# EchidnaShield_000.net
KiCad netlist of a schematic drawn in EAGLE
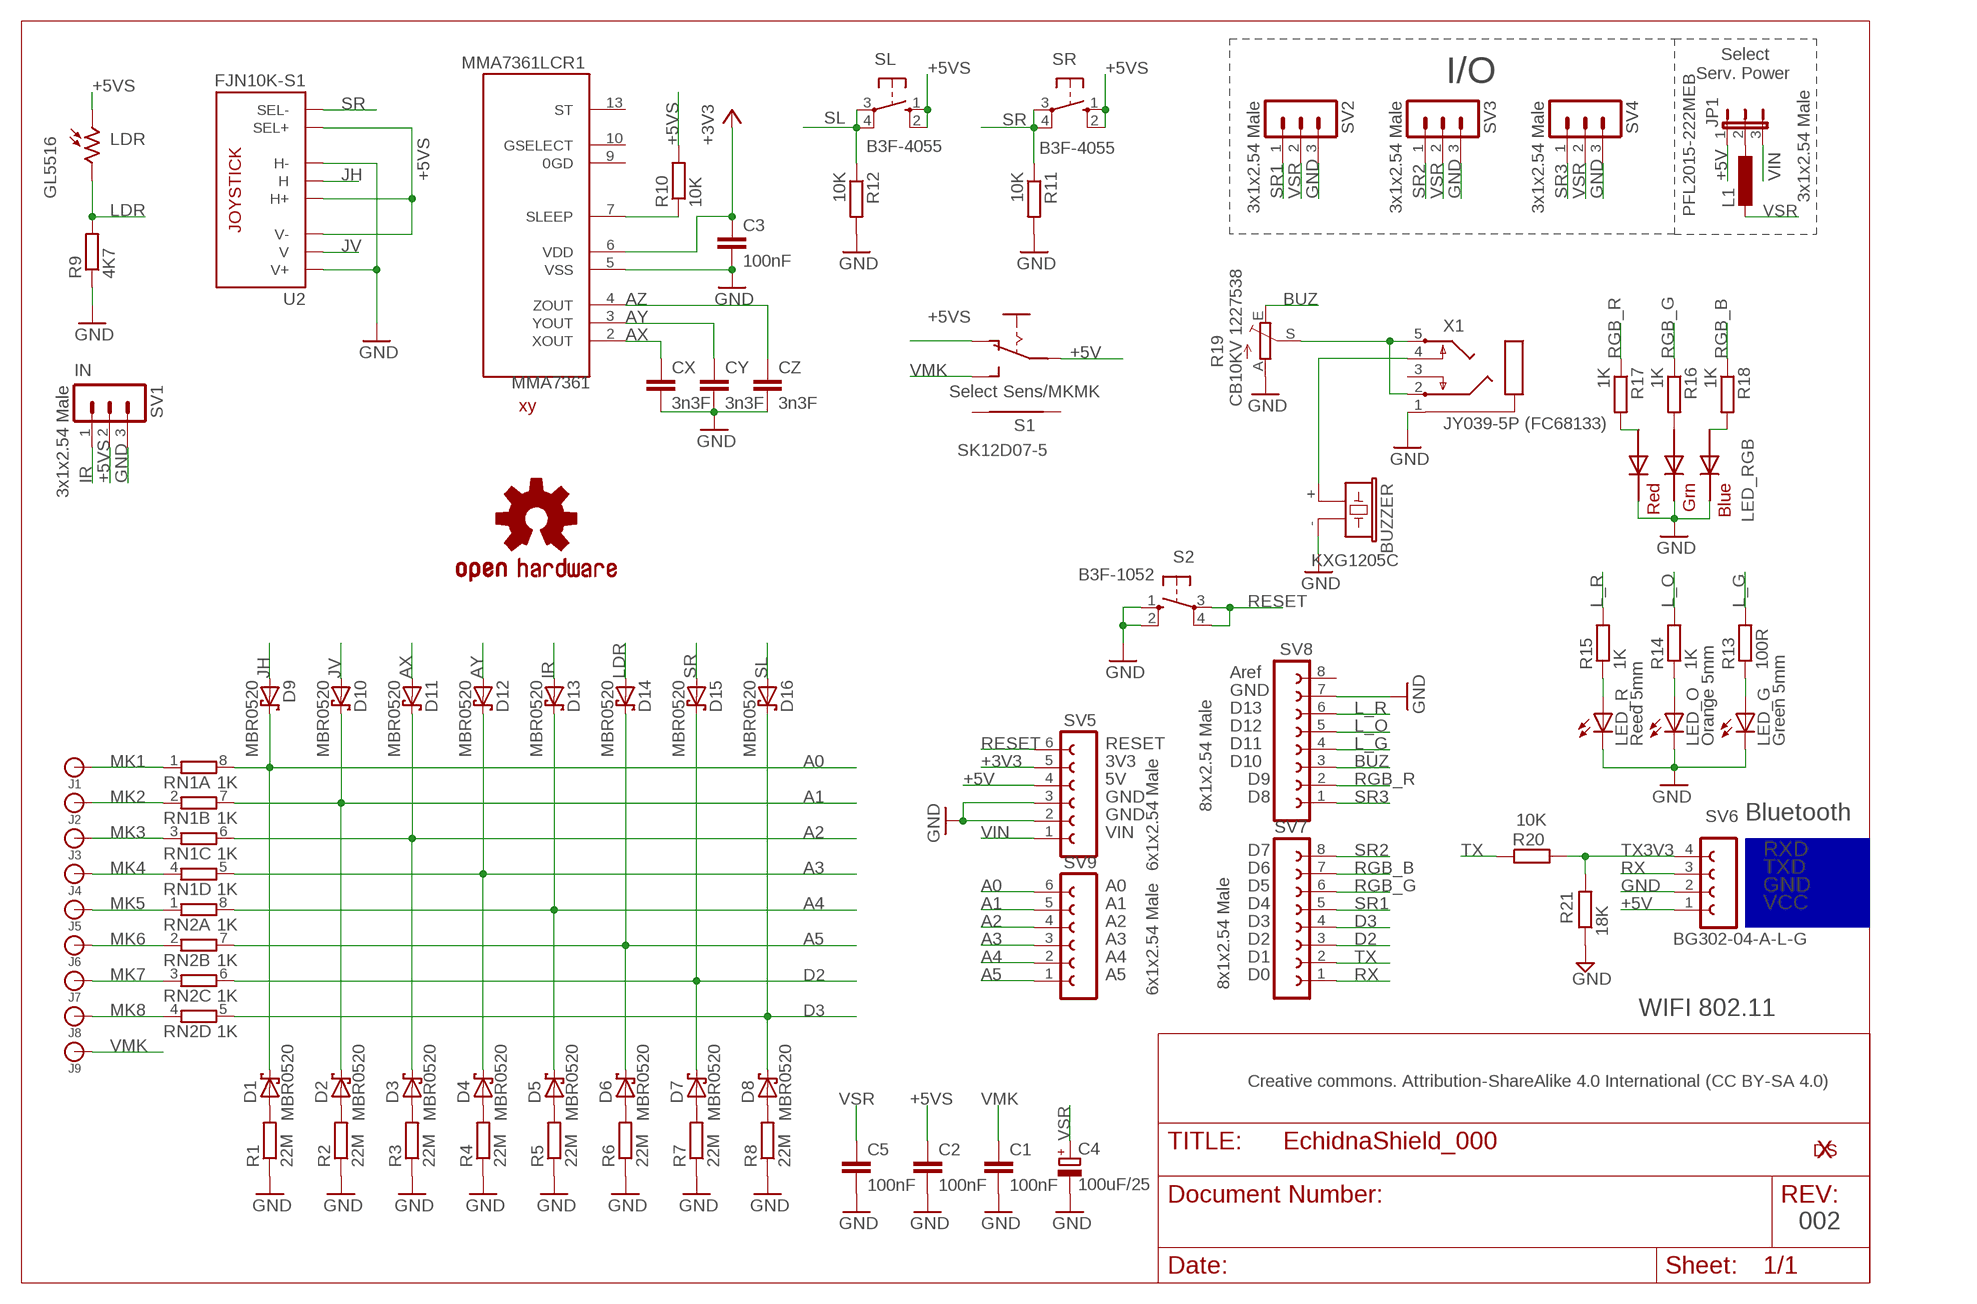
[diagram p0: schematic, sheet 1]

(export (version "E")
  (design (tool "Eeschema 10.0.6"))
  (components
    (comp (ref "BUZZER")
      (value "KXG1205C")
      (footprint "eagle-import:F_CM12P")
      (libsource (lib "eagle-import") (part "F/CM12P"))
    )
    (comp (ref "C1")
      (value "100nF")
      (footprint "eagle-import:C0603K")
      (libsource (lib "eagle-import") (part "C-EUC0603K"))
    )
    (comp (ref "C2")
      (value "100nF")
      (footprint "eagle-import:C0603K")
      (libsource (lib "eagle-import") (part "C-EUC0603K"))
    )
    (comp (ref "C3")
      (value "100nF")
      (footprint "eagle-import:C0603K")
      (libsource (lib "eagle-import") (part "C-EUC0603K"))
    )
    (comp (ref "C4")
      (value "100uF/25")
      (footprint "eagle-import:PANASONIC_D")
      (libsource (lib "eagle-import") (part "CPOL-EUD"))
    )
    (comp (ref "C5")
      (value "100nF")
      (footprint "eagle-import:C0603K")
      (libsource (lib "eagle-import") (part "C-EUC0603K"))
    )
    (comp (ref "CX")
      (value "3n3F")
      (footprint "eagle-import:C0603K")
      (libsource (lib "eagle-import") (part "C-EUC0603K"))
    )
    (comp (ref "CY")
      (value "3n3F")
      (footprint "eagle-import:C0603K")
      (libsource (lib "eagle-import") (part "C-EUC0603K"))
    )
    (comp (ref "CZ")
      (value "3n3F")
      (footprint "eagle-import:C0603K")
      (libsource (lib "eagle-import") (part "C-EUC0603K"))
    )
    (comp (ref "D1")
      (value "MBR0520")
      (footprint "eagle-import:SOD123FL")
      (libsource (lib "eagle-import") (part "SCHOTTKY-DIODESOD123FL"))
    )
    (comp (ref "D2")
      (value "MBR0520")
      (footprint "eagle-import:SOD123FL")
      (libsource (lib "eagle-import") (part "SCHOTTKY-DIODESOD123FL"))
    )
    (comp (ref "D3")
      (value "MBR0520")
      (footprint "eagle-import:SOD123FL")
      (libsource (lib "eagle-import") (part "SCHOTTKY-DIODESOD123FL"))
    )
    (comp (ref "D4")
      (value "MBR0520")
      (footprint "eagle-import:SOD123FL")
      (libsource (lib "eagle-import") (part "SCHOTTKY-DIODESOD123FL"))
    )
    (comp (ref "D5")
      (value "MBR0520")
      (footprint "eagle-import:SOD123FL")
      (libsource (lib "eagle-import") (part "SCHOTTKY-DIODESOD123FL"))
    )
    (comp (ref "D6")
      (value "MBR0520")
      (footprint "eagle-import:SOD123FL")
      (libsource (lib "eagle-import") (part "SCHOTTKY-DIODESOD123FL"))
    )
    (comp (ref "D7")
      (value "MBR0520")
      (footprint "eagle-import:SOD123FL")
      (libsource (lib "eagle-import") (part "SCHOTTKY-DIODESOD123FL"))
    )
    (comp (ref "D8")
      (value "MBR0520")
      (footprint "eagle-import:SOD123FL")
      (libsource (lib "eagle-import") (part "SCHOTTKY-DIODESOD123FL"))
    )
    (comp (ref "D9")
      (value "MBR0520")
      (footprint "eagle-import:SOD123FL")
      (libsource (lib "eagle-import") (part "SCHOTTKY-DIODESOD123FL"))
    )
    (comp (ref "D10")
      (value "MBR0520")
      (footprint "eagle-import:SOD123FL")
      (libsource (lib "eagle-import") (part "SCHOTTKY-DIODESOD123FL"))
    )
    (comp (ref "D11")
      (value "MBR0520")
      (footprint "eagle-import:SOD123FL")
      (libsource (lib "eagle-import") (part "SCHOTTKY-DIODESOD123FL"))
    )
    (comp (ref "D12")
      (value "MBR0520")
      (footprint "eagle-import:SOD123FL")
      (libsource (lib "eagle-import") (part "SCHOTTKY-DIODESOD123FL"))
    )
    (comp (ref "D13")
      (value "MBR0520")
      (footprint "eagle-import:SOD123FL")
      (libsource (lib "eagle-import") (part "SCHOTTKY-DIODESOD123FL"))
    )
    (comp (ref "D14")
      (value "MBR0520")
      (footprint "eagle-import:SOD123FL")
      (libsource (lib "eagle-import") (part "SCHOTTKY-DIODESOD123FL"))
    )
    (comp (ref "D15")
      (value "MBR0520")
      (footprint "eagle-import:SOD123FL")
      (libsource (lib "eagle-import") (part "SCHOTTKY-DIODESOD123FL"))
    )
    (comp (ref "D16")
      (value "MBR0520")
      (footprint "eagle-import:SOD123FL")
      (libsource (lib "eagle-import") (part "SCHOTTKY-DIODESOD123FL"))
    )
    (comp (ref "J1")
      (value "Hole")
      (footprint "eagle-import:BANANA_CONN")
      (libsource (lib "eagle-import") (part "BANANA_CONN"))
    )
    (comp (ref "J2")
      (value "Hole")
      (footprint "eagle-import:BANANA_CONN")
      (libsource (lib "eagle-import") (part "BANANA_CONN"))
    )
    (comp (ref "J3")
      (value "Hole")
      (footprint "eagle-import:BANANA_CONN")
      (libsource (lib "eagle-import") (part "BANANA_CONN"))
    )
    (comp (ref "J4")
      (value "Hole")
      (footprint "eagle-import:BANANA_CONN")
      (libsource (lib "eagle-import") (part "BANANA_CONN"))
    )
    (comp (ref "J5")
      (value "Hole")
      (footprint "eagle-import:BANANA_CONN")
      (libsource (lib "eagle-import") (part "BANANA_CONN"))
    )
    (comp (ref "J6")
      (value "Hole")
      (footprint "eagle-import:BANANA_CONN")
      (libsource (lib "eagle-import") (part "BANANA_CONN"))
    )
    (comp (ref "J7")
      (value "Hole")
      (footprint "eagle-import:BANANA_CONN")
      (libsource (lib "eagle-import") (part "BANANA_CONN"))
    )
    (comp (ref "J8")
      (value "Hole")
      (footprint "eagle-import:BANANA_CONN")
      (libsource (lib "eagle-import") (part "BANANA_CONN"))
    )
    (comp (ref "J9")
      (value "Hole")
      (footprint "eagle-import:BANANA_CONN")
      (libsource (lib "eagle-import") (part "BANANA_CONN"))
    )
    (comp (ref "JP1")
      (value "3x1x2.54 Male")
      (footprint "eagle-import:JUMPER_JP2")
      (libsource (lib "eagle-import") (part "JUMPER_JP2E"))
    )
    (comp (ref "L1")
      (value "PFL2015-222MEB")
      (footprint "eagle-import:L3216C")
      (libsource (lib "eagle-import") (part "L-EUL3216C"))
    )
    (comp (ref "LDR")
      (value "GL5516")
      (footprint "eagle-import:T0-46-A10XX")
      (libsource (lib "eagle-import") (part "A1060_34"))
    )
    (comp (ref "LED_G")
      (value "Green 5mm")
      (footprint "eagle-import:LED5MM")
      (libsource (lib "eagle-import") (part "LED5MM"))
    )
    (comp (ref "LED_O")
      (value "Orange 5mm")
      (footprint "eagle-import:LED5MM")
      (libsource (lib "eagle-import") (part "LED5MM"))
    )
    (comp (ref "LED_R")
      (value "Reed 5mm")
      (footprint "eagle-import:LED5MM")
      (libsource (lib "eagle-import") (part "LED5MM"))
    )
    (comp (ref "LED_RGB")
      (value "CPL6C-FKBN")
      (footprint "eagle-import:PLCC6")
      (libsource (lib "eagle-import") (part "CPL6C-FKBN"))
    )
    (comp (ref "LOGO1")
      (value "SPARKFUN-AESTHETICS_OSHW-LOGOL")
      (footprint "eagle-import:SPARKFUN-AESTHETICS_OSHW-LOGO-L")
      (libsource (lib "eagle-import") (part "SPARKFUN-AESTHETICS_OSHW-LOGOL"))
    )
    (comp (ref "MMA7361")
      (value "MMA7361LCR1")
      (footprint "eagle-import:LGA14")
      (libsource (lib "eagle-import") (part "MMA7361"))
    )
    (comp (ref "R1")
      (value "22M")
      (footprint "eagle-import:RCL_R0603")
      (libsource (lib "eagle-import") (part "RCL_R-EU_R0603"))
    )
    (comp (ref "R2")
      (value "22M")
      (footprint "eagle-import:RCL_R0603")
      (libsource (lib "eagle-import") (part "RCL_R-EU_R0603"))
    )
    (comp (ref "R3")
      (value "22M")
      (footprint "eagle-import:RCL_R0603")
      (libsource (lib "eagle-import") (part "RCL_R-EU_R0603"))
    )
    (comp (ref "R4")
      (value "22M")
      (footprint "eagle-import:RCL_R0603")
      (libsource (lib "eagle-import") (part "RCL_R-EU_R0603"))
    )
    (comp (ref "R5")
      (value "22M")
      (footprint "eagle-import:RCL_R0603")
      (libsource (lib "eagle-import") (part "RCL_R-EU_R0603"))
    )
    (comp (ref "R6")
      (value "22M")
      (footprint "eagle-import:RCL_R0603")
      (libsource (lib "eagle-import") (part "RCL_R-EU_R0603"))
    )
    (comp (ref "R7")
      (value "22M")
      (footprint "eagle-import:RCL_R0603")
      (libsource (lib "eagle-import") (part "RCL_R-EU_R0603"))
    )
    (comp (ref "R8")
      (value "22M")
      (footprint "eagle-import:RCL_R0603")
      (libsource (lib "eagle-import") (part "RCL_R-EU_R0603"))
    )
    (comp (ref "R9")
      (value "4K7")
      (footprint "eagle-import:RCL_R0603")
      (libsource (lib "eagle-import") (part "RCL_R-EU_R0603"))
    )
    (comp (ref "R10")
      (value "10K")
      (footprint "eagle-import:RCL_R0603")
      (libsource (lib "eagle-import") (part "RCL_R-EU_R0603"))
    )
    (comp (ref "R11")
      (value "10K")
      (footprint "eagle-import:RCL_R0603")
      (libsource (lib "eagle-import") (part "RCL_R-EU_R0603"))
    )
    (comp (ref "R12")
      (value "10K")
      (footprint "eagle-import:RCL_R0603")
      (libsource (lib "eagle-import") (part "RCL_R-EU_R0603"))
    )
    (comp (ref "R13")
      (value "100R")
      (footprint "eagle-import:RCL_R0603")
      (libsource (lib "eagle-import") (part "RCL_R-EU_R0603"))
    )
    (comp (ref "R14")
      (value "1K")
      (footprint "eagle-import:RCL_R0603")
      (libsource (lib "eagle-import") (part "RCL_R-EU_R0603"))
    )
    (comp (ref "R15")
      (value "1K")
      (footprint "eagle-import:RCL_R0603")
      (libsource (lib "eagle-import") (part "RCL_R-EU_R0603"))
    )
    (comp (ref "R16")
      (value "1K")
      (footprint "eagle-import:RCL_R0603")
      (libsource (lib "eagle-import") (part "RCL_R-EU_R0603"))
    )
    (comp (ref "R17")
      (value "1K")
      (footprint "eagle-import:RCL_R0603")
      (libsource (lib "eagle-import") (part "RCL_R-EU_R0603"))
    )
    (comp (ref "R18")
      (value "1K")
      (footprint "eagle-import:RCL_R0603")
      (libsource (lib "eagle-import") (part "RCL_R-EU_R0603"))
    )
    (comp (ref "R19")
      (value "CB10KV 1227538")
      (footprint "eagle-import:CA9V")
      (libsource (lib "eagle-import") (part "TRIM_EU-CA9V"))
    )
    (comp (ref "R20")
      (value "10K")
      (footprint "eagle-import:R0603")
      (libsource (lib "eagle-import") (part "R-EU_R0603"))
    )
    (comp (ref "R21")
      (value "18K")
      (footprint "eagle-import:R0603")
      (libsource (lib "eagle-import") (part "R-EU_R0603"))
    )
    (comp (ref "RN1")
      (value "1K")
      (footprint "eagle-import:RESISTOR-DIL_0603-ARC")
      (libsource (lib "eagle-import") (part "RESISTOR-DIL_4R-N0603-ARC"))
    )
    (comp (ref "RN2")
      (value "1K")
      (footprint "eagle-import:RESISTOR-DIL_0603-ARC")
      (libsource (lib "eagle-import") (part "RESISTOR-DIL_4R-N0603-ARC"))
    )
    (comp (ref "S1")
      (value "SK12D07-5")
      (footprint "eagle-import:ESCORNA_SK-12D07")
      (libsource (lib "eagle-import") (part "ESCORNA_SK12F14D"))
    )
    (comp (ref "S2")
      (value "B3F-1052")
      (footprint "eagle-import:SWITCH-OMRON_B3F-10XX")
      (fields (field (name "MPN") "B3F-1000"))
      (libsource (lib "eagle-import") (part "SWITCH-OMRON_10-XX"))
    )
    (comp (ref "SL")
      (value "B3F-4055")
      (footprint "eagle-import:B3F-40XX")
      (fields (field (name "MF") "OMRON COMPONENTS USA") (field (name "MPN") "B3F-4000"))
      (libsource (lib "eagle-import") (part "40-XX"))
    )
    (comp (ref "SR")
      (value "B3F-4055")
      (footprint "eagle-import:B3F-40XX")
      (fields (field (name "MF") "OMRON COMPONENTS USA") (field (name "MPN") "B3F-4000"))
      (libsource (lib "eagle-import") (part "40-XX"))
    )
    (comp (ref "SV1")
      (value "3x1x2.54 Male")
      (footprint "eagle-import:MA03-1")
      (libsource (lib "eagle-import") (part "MA03-1"))
    )
    (comp (ref "SV2")
      (value "3x1x2.54 Male")
      (footprint "eagle-import:MA03-1")
      (libsource (lib "eagle-import") (part "MA03-1"))
    )
    (comp (ref "SV3")
      (value "3x1x2.54 Male")
      (footprint "eagle-import:MA03-1")
      (libsource (lib "eagle-import") (part "MA03-1"))
    )
    (comp (ref "SV4")
      (value "3x1x2.54 Male")
      (footprint "eagle-import:MA03-1")
      (libsource (lib "eagle-import") (part "MA03-1"))
    )
    (comp (ref "SV5")
      (value "6x1x2.54 Male")
      (footprint "eagle-import:FE06")
      (libsource (lib "eagle-import") (part "FE06-1"))
    )
    (comp (ref "SV6")
      (value "BG302-04-A-L-G")
      (footprint "eagle-import:FE04W")
      (libsource (lib "eagle-import") (part "FE04W"))
    )
    (comp (ref "SV7")
      (value "8x1x2.54 Male")
      (footprint "eagle-import:FE08")
      (libsource (lib "eagle-import") (part "FE08-1"))
    )
    (comp (ref "SV8")
      (value "8x1x2.54 Male")
      (footprint "eagle-import:FE08")
      (libsource (lib "eagle-import") (part "FE08-1"))
    )
    (comp (ref "SV9")
      (value "6x1x2.54 Male")
      (footprint "eagle-import:FE06")
      (libsource (lib "eagle-import") (part "FE06-1"))
    )
    (comp (ref "U$2") (value "XY") (footprint "eagle-import:XY") (libsource (lib "eagle-import") (part "XY")))
    (comp (ref "U$5")
      (value "XDESIG21")
      (footprint "eagle-import:XDESIG")
      (libsource (lib "eagle-import") (part "XDESIG21"))
    )
    (comp (ref "U2")
      (value "FJN10K-S1")
      (footprint "eagle-import:JOYSTICK")
      (libsource (lib "eagle-import") (part "JOYSTICKPTH"))
    )
    (comp (ref "X1")
      (value "JY039-5P (FC68133)")
      (footprint "eagle-import:STX3100")
      (libsource (lib "eagle-import") (part "STEREOJACK"))
    )
  )
  (nets
    (net (code "1") (name "+3V3") (class "Default")
      (node (ref "C3") (pin "1") (pinfunction "1_1") (pintype "passive"))
      (node (ref "MMA7361") (pin "6") (pinfunction "VDD_6") (pintype "bidirectional"))
      (node (ref "SV5") (pin "5") (pinfunction "5_5") (pintype "passive"))
    )
    (net (code "2") (name "/+5V") (class "Default")
      (node (ref "JP1") (pin "1") (pinfunction "1_1") (pintype "passive"))
      (node (ref "S1") (pin "P$1") (pinfunction "P_P$1") (pintype "passive"))
      (node (ref "SV5") (pin "4") (pinfunction "4_4") (pintype "passive"))
      (node (ref "SV6") (pin "1") (pinfunction "1_1") (pintype "passive"))
    )
    (net (code "3") (name "/+5VS") (class "Default")
      (node (ref "C2") (pin "1") (pinfunction "1_1") (pintype "passive"))
      (node (ref "LDR") (pin "1") (pinfunction "1_1") (pintype "passive"))
      (node (ref "R10") (pin "2") (pinfunction "2_2") (pintype "passive"))
      (node (ref "S1") (pin "P$2") (pinfunction "O_P$2") (pintype "passive"))
      (node (ref "SL") (pin "1") (pinfunction "S_1") (pintype "passive"))
      (node (ref "SL") (pin "2") (pinfunction "S1_2") (pintype "passive"))
      (node (ref "SR") (pin "1") (pinfunction "S_1") (pintype "passive"))
      (node (ref "SR") (pin "2") (pinfunction "S1_2") (pintype "passive"))
      (node (ref "SV1") (pin "2") (pinfunction "2_2") (pintype "passive"))
      (node (ref "U2") (pin "B1A") (pinfunction "SEL+_B1A") (pintype "bidirectional"))
      (node (ref "U2") (pin "H1") (pinfunction "H+_H1") (pintype "bidirectional"))
      (node (ref "U2") (pin "V3") (pinfunction "V-_V3") (pintype "bidirectional"))
    )
    (net (code "4") (name "/A0") (class "Default")
      (node (ref "D1") (pin "C") (pinfunction "C_C") (pintype "passive"))
      (node (ref "D9") (pin "C") (pinfunction "C_C") (pintype "passive"))
      (node (ref "RN1") (pin "8") (pinfunction "2_8") (pintype "passive"))
      (node (ref "SV9") (pin "6") (pinfunction "6_6") (pintype "passive"))
    )
    (net (code "5") (name "/A1") (class "Default")
      (node (ref "D10") (pin "C") (pinfunction "C_C") (pintype "passive"))
      (node (ref "D2") (pin "C") (pinfunction "C_C") (pintype "passive"))
      (node (ref "RN1") (pin "7") (pinfunction "2_7") (pintype "passive"))
      (node (ref "SV9") (pin "5") (pinfunction "5_5") (pintype "passive"))
    )
    (net (code "6") (name "/A2") (class "Default")
      (node (ref "D11") (pin "C") (pinfunction "C_C") (pintype "passive"))
      (node (ref "D3") (pin "C") (pinfunction "C_C") (pintype "passive"))
      (node (ref "RN1") (pin "6") (pinfunction "2_6") (pintype "passive"))
      (node (ref "SV9") (pin "4") (pinfunction "4_4") (pintype "passive"))
    )
    (net (code "7") (name "/A3") (class "Default")
      (node (ref "D12") (pin "C") (pinfunction "C_C") (pintype "passive"))
      (node (ref "D4") (pin "C") (pinfunction "C_C") (pintype "passive"))
      (node (ref "RN1") (pin "5") (pinfunction "2_5") (pintype "passive"))
      (node (ref "SV9") (pin "3") (pinfunction "3_3") (pintype "passive"))
    )
    (net (code "8") (name "/A4") (class "Default")
      (node (ref "D13") (pin "C") (pinfunction "C_C") (pintype "passive"))
      (node (ref "D5") (pin "C") (pinfunction "C_C") (pintype "passive"))
      (node (ref "RN2") (pin "8") (pinfunction "2_8") (pintype "passive"))
      (node (ref "SV9") (pin "2") (pinfunction "2_2") (pintype "passive"))
    )
    (net (code "9") (name "/A5") (class "Default")
      (node (ref "D14") (pin "C") (pinfunction "C_C") (pintype "passive"))
      (node (ref "D6") (pin "C") (pinfunction "C_C") (pintype "passive"))
      (node (ref "RN2") (pin "7") (pinfunction "2_7") (pintype "passive"))
      (node (ref "SV9") (pin "1") (pinfunction "1_1") (pintype "passive"))
    )
    (net (code "10") (name "/AX") (class "Default")
      (node (ref "CX") (pin "1") (pinfunction "1_1") (pintype "passive"))
      (node (ref "D11") (pin "A") (pinfunction "A_A") (pintype "passive"))
      (node (ref "MMA7361") (pin "2") (pinfunction "XOUT_2") (pintype "bidirectional"))
    )
    (net (code "11") (name "/AY") (class "Default")
      (node (ref "CY") (pin "1") (pinfunction "1_1") (pintype "passive"))
      (node (ref "D12") (pin "A") (pinfunction "A_A") (pintype "passive"))
      (node (ref "MMA7361") (pin "3") (pinfunction "YOUT_3") (pintype "bidirectional"))
    )
    (net (code "12") (name "/AZ") (class "Default")
      (node (ref "CZ") (pin "1") (pinfunction "1_1") (pintype "passive"))
      (node (ref "MMA7361") (pin "4") (pinfunction "ZOUT_4") (pintype "bidirectional"))
    )
    (net (code "13") (name "/BUZ") (class "Default")
      (node (ref "R19") (pin "E") (pinfunction "E_E") (pintype "passive"))
      (node (ref "SV8") (pin "3") (pinfunction "3_3") (pintype "passive"))
    )
    (net (code "14") (name "/D2") (class "Default")
      (node (ref "D15") (pin "C") (pinfunction "C_C") (pintype "passive"))
      (node (ref "D7") (pin "C") (pinfunction "C_C") (pintype "passive"))
      (node (ref "RN2") (pin "6") (pinfunction "2_6") (pintype "passive"))
      (node (ref "SV7") (pin "3") (pinfunction "3_3") (pintype "passive"))
    )
    (net (code "15") (name "/D3") (class "Default")
      (node (ref "D16") (pin "C") (pinfunction "C_C") (pintype "passive"))
      (node (ref "D8") (pin "C") (pinfunction "C_C") (pintype "passive"))
      (node (ref "RN2") (pin "5") (pinfunction "2_5") (pintype "passive"))
      (node (ref "SV7") (pin "4") (pinfunction "4_4") (pintype "passive"))
    )
    (net (code "16") (name "/IR") (class "Default")
      (node (ref "D13") (pin "A") (pinfunction "A_A") (pintype "passive"))
      (node (ref "SV1") (pin "1") (pinfunction "1_1") (pintype "passive"))
    )
    (net (code "17") (name "/JH") (class "Default")
      (node (ref "D9") (pin "A") (pinfunction "A_A") (pintype "passive"))
      (node (ref "U2") (pin "H2") (pinfunction "H_H2") (pintype "bidirectional"))
    )
    (net (code "18") (name "/JV") (class "Default")
      (node (ref "D10") (pin "A") (pinfunction "A_A") (pintype "passive"))
      (node (ref "U2") (pin "V2") (pinfunction "V_V2") (pintype "bidirectional"))
    )
    (net (code "19") (name "/LDR") (class "Default")
      (node (ref "D14") (pin "A") (pinfunction "A_A") (pintype "passive"))
      (node (ref "LDR") (pin "2") (pinfunction "2_2") (pintype "passive"))
      (node (ref "R9") (pin "2") (pinfunction "2_2") (pintype "passive"))
    )
    (net (code "20") (name "/L_G") (class "Default")
      (node (ref "R13") (pin "2") (pinfunction "2_2") (pintype "passive"))
      (node (ref "SV8") (pin "4") (pinfunction "4_4") (pintype "passive"))
    )
    (net (code "21") (name "/L_O") (class "Default")
      (node (ref "R14") (pin "2") (pinfunction "2_2") (pintype "passive"))
      (node (ref "SV8") (pin "5") (pinfunction "5_5") (pintype "passive"))
    )
    (net (code "22") (name "/L_R") (class "Default")
      (node (ref "R15") (pin "2") (pinfunction "2_2") (pintype "passive"))
      (node (ref "SV8") (pin "6") (pinfunction "6_6") (pintype "passive"))
    )
    (net (code "23") (name "/MK1") (class "Default")
      (node (ref "J1") (pin "P$1") (pinfunction "1_P$1") (pintype "passive"))
      (node (ref "RN1") (pin "1") (pinfunction "1_1") (pintype "passive"))
    )
    (net (code "24") (name "/MK2") (class "Default")
      (node (ref "J2") (pin "P$1") (pinfunction "1_P$1") (pintype "passive"))
      (node (ref "RN1") (pin "2") (pinfunction "1_2") (pintype "passive"))
    )
    (net (code "25") (name "/MK3") (class "Default")
      (node (ref "J3") (pin "P$1") (pinfunction "1_P$1") (pintype "passive"))
      (node (ref "RN1") (pin "3") (pinfunction "1_3") (pintype "passive"))
    )
    (net (code "26") (name "/MK4") (class "Default")
      (node (ref "J4") (pin "P$1") (pinfunction "1_P$1") (pintype "passive"))
      (node (ref "RN1") (pin "4") (pinfunction "1_4") (pintype "passive"))
    )
    (net (code "27") (name "/MK5") (class "Default")
      (node (ref "J5") (pin "P$1") (pinfunction "1_P$1") (pintype "passive"))
      (node (ref "RN2") (pin "1") (pinfunction "1_1") (pintype "passive"))
    )
    (net (code "28") (name "/MK6") (class "Default")
      (node (ref "J6") (pin "P$1") (pinfunction "1_P$1") (pintype "passive"))
      (node (ref "RN2") (pin "2") (pinfunction "1_2") (pintype "passive"))
    )
    (net (code "29") (name "/MK7") (class "Default")
      (node (ref "J7") (pin "P$1") (pinfunction "1_P$1") (pintype "passive"))
      (node (ref "RN2") (pin "3") (pinfunction "1_3") (pintype "passive"))
    )
    (net (code "30") (name "/MK8") (class "Default")
      (node (ref "J8") (pin "P$1") (pinfunction "1_P$1") (pintype "passive"))
      (node (ref "RN2") (pin "4") (pinfunction "1_4") (pintype "passive"))
    )
    (net (code "31") (name "/RESET") (class "Default")
      (node (ref "S2") (pin "3") (pinfunction "P_3") (pintype "passive"))
      (node (ref "S2") (pin "4") (pinfunction "P1_4") (pintype "passive"))
      (node (ref "SV5") (pin "6") (pinfunction "6_6") (pintype "passive"))
    )
    (net (code "32") (name "/RGB_B") (class "Default")
      (node (ref "R18") (pin "1") (pinfunction "1_1") (pintype "passive"))
      (node (ref "SV7") (pin "7") (pinfunction "7_7") (pintype "passive"))
    )
    (net (code "33") (name "/RGB_G") (class "Default")
      (node (ref "R16") (pin "1") (pinfunction "1_1") (pintype "passive"))
      (node (ref "SV7") (pin "6") (pinfunction "6_6") (pintype "passive"))
    )
    (net (code "34") (name "/RGB_R") (class "Default")
      (node (ref "R17") (pin "1") (pinfunction "1_1") (pintype "passive"))
      (node (ref "SV8") (pin "2") (pinfunction "2_2") (pintype "passive"))
    )
    (net (code "35") (name "/RX") (class "Default")
      (node (ref "SV6") (pin "3") (pinfunction "3_3") (pintype "passive"))
      (node (ref "SV7") (pin "1") (pinfunction "1_1") (pintype "passive"))
    )
    (net (code "36") (name "/SL") (class "Default")
      (node (ref "D16") (pin "A") (pinfunction "A_A") (pintype "passive"))
      (node (ref "R12") (pin "1") (pinfunction "1_1") (pintype "passive"))
      (node (ref "SL") (pin "3") (pinfunction "P_3") (pintype "passive"))
      (node (ref "SL") (pin "4") (pinfunction "P1_4") (pintype "passive"))
    )
    (net (code "37") (name "/SR") (class "Default")
      (node (ref "D15") (pin "A") (pinfunction "A_A") (pintype "passive"))
      (node (ref "R11") (pin "1") (pinfunction "1_1") (pintype "passive"))
      (node (ref "SR") (pin "3") (pinfunction "P_3") (pintype "passive"))
      (node (ref "SR") (pin "4") (pinfunction "P1_4") (pintype "passive"))
      (node (ref "U2") (pin "B2A") (pinfunction "SEL-_B2A") (pintype "bidirectional"))
    )
    (net (code "38") (name "/SR1") (class "Default")
      (node (ref "SV2") (pin "1") (pinfunction "1_1") (pintype "passive"))
      (node (ref "SV7") (pin "5") (pinfunction "5_5") (pintype "passive"))
    )
    (net (code "39") (name "/SR2") (class "Default")
      (node (ref "SV3") (pin "1") (pinfunction "1_1") (pintype "passive"))
      (node (ref "SV7") (pin "8") (pinfunction "8_8") (pintype "passive"))
    )
    (net (code "40") (name "/SR3") (class "Default")
      (node (ref "SV4") (pin "1") (pinfunction "1_1") (pintype "passive"))
      (node (ref "SV8") (pin "1") (pinfunction "1_1") (pintype "passive"))
    )
    (net (code "41") (name "/TX") (class "Default")
      (node (ref "R20") (pin "1") (pinfunction "1_1") (pintype "passive"))
      (node (ref "SV7") (pin "2") (pinfunction "2_2") (pintype "passive"))
    )
    (net (code "42") (name "/TX3V3") (class "Default")
      (node (ref "R20") (pin "2") (pinfunction "2_2") (pintype "passive"))
      (node (ref "R21") (pin "2") (pinfunction "2_2") (pintype "passive"))
      (node (ref "SV6") (pin "4") (pinfunction "4_4") (pintype "passive"))
    )
    (net (code "43") (name "/VIN") (class "Default")
      (node (ref "JP1") (pin "3") (pinfunction "3_3") (pintype "passive"))
      (node (ref "SV5") (pin "1") (pinfunction "1_1") (pintype "passive"))
    )
    (net (code "44") (name "/VMK") (class "Default")
      (node (ref "C1") (pin "1") (pinfunction "1_1") (pintype "passive"))
      (node (ref "J9") (pin "P$1") (pinfunction "1_P$1") (pintype "passive"))
      (node (ref "S1") (pin "P$3") (pinfunction "S_P$3") (pintype "passive"))
    )
    (net (code "45") (name "/VSR") (class "Default")
      (node (ref "C4") (pin "+") (pinfunction "+_+") (pintype "passive"))
      (node (ref "C5") (pin "1") (pinfunction "1_1") (pintype "passive"))
      (node (ref "L1") (pin "2") (pinfunction "2_2") (pintype "passive"))
      (node (ref "SV2") (pin "2") (pinfunction "2_2") (pintype "passive"))
      (node (ref "SV3") (pin "2") (pinfunction "2_2") (pintype "passive"))
      (node (ref "SV4") (pin "2") (pinfunction "2_2") (pintype "passive"))
    )
    (net (code "46") (name "GND") (class "Default")
      (node (ref "BUZZER") (pin "-") (pinfunction "2_-") (pintype "passive"))
      (node (ref "C1") (pin "2") (pinfunction "2_2") (pintype "passive"))
      (node (ref "C2") (pin "2") (pinfunction "2_2") (pintype "passive"))
      (node (ref "C3") (pin "2") (pinfunction "2_2") (pintype "passive"))
      (node (ref "C4") (pin "-") (pinfunction "-_-") (pintype "passive"))
      (node (ref "C5") (pin "2") (pinfunction "2_2") (pintype "passive"))
      (node (ref "CX") (pin "2") (pinfunction "2_2") (pintype "passive"))
      (node (ref "CY") (pin "2") (pinfunction "2_2") (pintype "passive"))
      (node (ref "CZ") (pin "2") (pinfunction "2_2") (pintype "passive"))
      (node (ref "LED_G") (pin "K") (pinfunction "C_K") (pintype "passive"))
      (node (ref "LED_O") (pin "K") (pinfunction "C_K") (pintype "passive"))
      (node (ref "LED_R") (pin "K") (pinfunction "C_K") (pintype "passive"))
      (node (ref "LED_RGB") (pin "4") (pinfunction "BLUE_C_4") (pintype "bidirectional"))
      (node (ref "LED_RGB") (pin "5") (pinfunction "GREEN_C_5") (pintype "bidirectional"))
      (node (ref "LED_RGB") (pin "6") (pinfunction "RED_C_6") (pintype "bidirectional"))
      (node (ref "MMA7361") (pin "5") (pinfunction "VSS_5") (pintype "bidirectional"))
      (node (ref "R1") (pin "1") (pinfunction "1_1") (pintype "passive"))
      (node (ref "R11") (pin "2") (pinfunction "2_2") (pintype "passive"))
      (node (ref "R12") (pin "2") (pinfunction "2_2") (pintype "passive"))
      (node (ref "R19") (pin "A") (pinfunction "A_A") (pintype "passive"))
      (node (ref "R2") (pin "1") (pinfunction "1_1") (pintype "passive"))
      (node (ref "R21") (pin "1") (pinfunction "1_1") (pintype "passive"))
      (node (ref "R3") (pin "1") (pinfunction "1_1") (pintype "passive"))
      (node (ref "R4") (pin "1") (pinfunction "1_1") (pintype "passive"))
      (node (ref "R5") (pin "1") (pinfunction "1_1") (pintype "passive"))
      (node (ref "R6") (pin "1") (pinfunction "1_1") (pintype "passive"))
      (node (ref "R7") (pin "1") (pinfunction "1_1") (pintype "passive"))
      (node (ref "R8") (pin "1") (pinfunction "1_1") (pintype "passive"))
      (node (ref "R9") (pin "1") (pinfunction "1_1") (pintype "passive"))
      (node (ref "S2") (pin "1") (pinfunction "S_1") (pintype "passive"))
      (node (ref "S2") (pin "2") (pinfunction "S1_2") (pintype "passive"))
      (node (ref "SV1") (pin "3") (pinfunction "3_3") (pintype "passive"))
      (node (ref "SV2") (pin "3") (pinfunction "3_3") (pintype "passive"))
      (node (ref "SV3") (pin "3") (pinfunction "3_3") (pintype "passive"))
      (node (ref "SV4") (pin "3") (pinfunction "3_3") (pintype "passive"))
      (node (ref "SV5") (pin "2") (pinfunction "2_2") (pintype "passive"))
      (node (ref "SV5") (pin "3") (pinfunction "3_3") (pintype "passive"))
      (node (ref "SV6") (pin "2") (pinfunction "2_2") (pintype "passive"))
      (node (ref "SV8") (pin "7") (pinfunction "7_7") (pintype "passive"))
      (node (ref "U2") (pin "H3") (pinfunction "H-_H3") (pintype "bidirectional"))
      (node (ref "U2") (pin "V1") (pinfunction "V+_V1") (pintype "bidirectional"))
      (node (ref "X1") (pin "1") (pinfunction "1_1") (pintype "passive"))
    )
    (net (code "47") (name "Net-(BUZZER-1)") (class "Default")
      (node (ref "BUZZER") (pin "+") (pinfunction "1_+") (pintype "passive"))
      (node (ref "X1") (pin "4") (pinfunction "4_4") (pintype "passive"))
    )
    (net (code "48") (name "Net-(D1-PadA)") (class "Default")
      (node (ref "D1") (pin "A") (pinfunction "A_A") (pintype "passive"))
      (node (ref "R1") (pin "2") (pinfunction "2_2") (pintype "passive"))
    )
    (net (code "49") (name "Net-(D2-PadA)") (class "Default")
      (node (ref "D2") (pin "A") (pinfunction "A_A") (pintype "passive"))
      (node (ref "R2") (pin "2") (pinfunction "2_2") (pintype "passive"))
    )
    (net (code "50") (name "Net-(D3-PadA)") (class "Default")
      (node (ref "D3") (pin "A") (pinfunction "A_A") (pintype "passive"))
      (node (ref "R3") (pin "2") (pinfunction "2_2") (pintype "passive"))
    )
    (net (code "51") (name "Net-(D4-PadA)") (class "Default")
      (node (ref "D4") (pin "A") (pinfunction "A_A") (pintype "passive"))
      (node (ref "R4") (pin "2") (pinfunction "2_2") (pintype "passive"))
    )
    (net (code "52") (name "Net-(D5-PadA)") (class "Default")
      (node (ref "D5") (pin "A") (pinfunction "A_A") (pintype "passive"))
      (node (ref "R5") (pin "2") (pinfunction "2_2") (pintype "passive"))
    )
    (net (code "53") (name "Net-(D6-PadA)") (class "Default")
      (node (ref "D6") (pin "A") (pinfunction "A_A") (pintype "passive"))
      (node (ref "R6") (pin "2") (pinfunction "2_2") (pintype "passive"))
    )
    (net (code "54") (name "Net-(D7-PadA)") (class "Default")
      (node (ref "D7") (pin "A") (pinfunction "A_A") (pintype "passive"))
      (node (ref "R7") (pin "2") (pinfunction "2_2") (pintype "passive"))
    )
    (net (code "55") (name "Net-(D8-PadA)") (class "Default")
      (node (ref "D8") (pin "A") (pinfunction "A_A") (pintype "passive"))
      (node (ref "R8") (pin "2") (pinfunction "2_2") (pintype "passive"))
    )
    (net (code "56") (name "Net-(JP1-Pad2)") (class "Default")
      (node (ref "JP1") (pin "2") (pinfunction "2_2") (pintype "passive"))
      (node (ref "L1") (pin "1") (pinfunction "1_1") (pintype "passive"))
    )
    (net (code "57") (name "Net-(LED_G-PadA)") (class "Default")
      (node (ref "LED_G") (pin "A") (pinfunction "A_A") (pintype "passive"))
      (node (ref "R13") (pin "1") (pinfunction "1_1") (pintype "passive"))
    )
    (net (code "58") (name "Net-(LED_O-PadA)") (class "Default")
      (node (ref "LED_O") (pin "A") (pinfunction "A_A") (pintype "passive"))
      (node (ref "R14") (pin "1") (pinfunction "1_1") (pintype "passive"))
    )
    (net (code "59") (name "Net-(LED_R-PadA)") (class "Default")
      (node (ref "LED_R") (pin "A") (pinfunction "A_A") (pintype "passive"))
      (node (ref "R15") (pin "1") (pinfunction "1_1") (pintype "passive"))
    )
    (net (code "60") (name "Net-(LED_RGB-BLUE_A)") (class "Default")
      (node (ref "LED_RGB") (pin "3") (pinfunction "BLUE_A_3") (pintype "bidirectional"))
      (node (ref "R18") (pin "2") (pinfunction "2_2") (pintype "passive"))
    )
    (net (code "61") (name "Net-(LED_RGB-GREEN_A)") (class "Default")
      (node (ref "LED_RGB") (pin "2") (pinfunction "GREEN_A_2") (pintype "bidirectional"))
      (node (ref "R16") (pin "2") (pinfunction "2_2") (pintype "passive"))
    )
    (net (code "62") (name "Net-(LED_RGB-RED_A)") (class "Default")
      (node (ref "LED_RGB") (pin "1") (pinfunction "RED_A_1") (pintype "bidirectional"))
      (node (ref "R17") (pin "2") (pinfunction "2_2") (pintype "passive"))
    )
    (net (code "63") (name "Net-(MMA7361-SLEEP)") (class "Default")
      (node (ref "MMA7361") (pin "7") (pinfunction "SLEEP_7") (pintype "bidirectional"))
      (node (ref "R10") (pin "1") (pinfunction "1_1") (pintype "passive"))
    )
    (net (code "64") (name "Net-(R19-PadS)") (class "Default")
      (node (ref "R19") (pin "S") (pinfunction "S_S") (pintype "passive"))
      (node (ref "X1") (pin "2") (pinfunction "2_2") (pintype "passive"))
      (node (ref "X1") (pin "5") (pinfunction "5_5") (pintype "passive"))
    )
    (net (code "65") (name "unconnected-(MMA7361-0GD-Pad9)") (class "Default")
      (node (ref "MMA7361") (pin "9") (pinfunction "0GD_9") (pintype "bidirectional"))
    )
    (net (code "66") (name "unconnected-(MMA7361-GSELECT-Pad10)") (class "Default")
      (node (ref "MMA7361") (pin "10") (pinfunction "GSELECT_10") (pintype "bidirectional"))
    )
    (net (code "67") (name "unconnected-(MMA7361-ST-Pad13)") (class "Default")
      (node (ref "MMA7361") (pin "13") (pinfunction "ST_13") (pintype "bidirectional"))
    )
    (net (code "68") (name "unconnected-(S1-P$1-PadP$4)") (class "Default")
      (node (ref "S1") (pin "P$4") (pinfunction "P$1_P$4") (pintype "passive"))
    )
    (net (code "69") (name "unconnected-(S1-P$2-PadP$5)") (class "Default")
      (node (ref "S1") (pin "P$5") (pinfunction "P$2_P$5") (pintype "bidirectional"))
    )
    (net (code "70") (name "unconnected-(SV8-Pad8)") (class "Default")
      (node (ref "SV8") (pin "8") (pinfunction "8_8") (pintype "passive"))
    )
    (net (code "71") (name "unconnected-(X1-Pad3)") (class "Default")
      (node (ref "X1") (pin "3") (pinfunction "3_3") (pintype "passive"))
    )
  )
)
